# MUSB_05_X_B_SM_A.net
KiCad netlist of a schematic drawn in Altium Designer
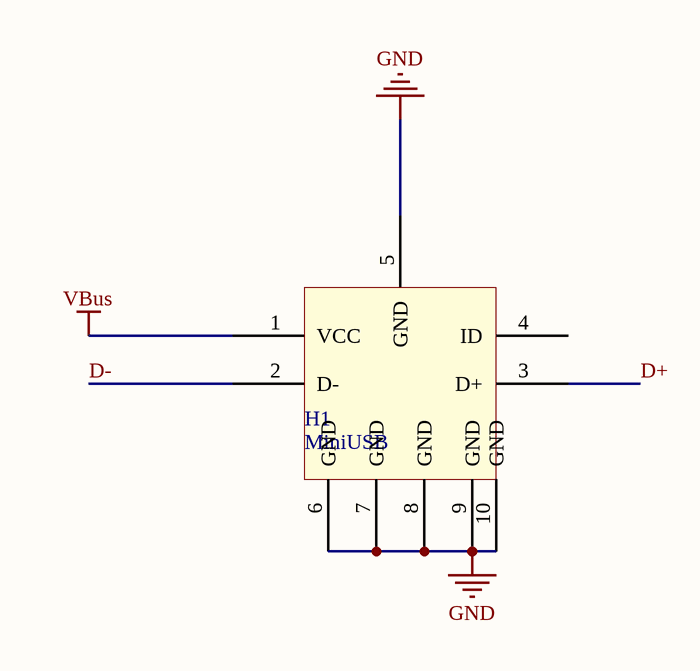
[diagram p0: MUSB_05_X_B_SM_A.SchDoc]

(export (version "E")
  (design (tool "Eeschema 10.0.6"))
  (components
    (comp (ref "H1")
      (value "MiniUSB")
      (footprint "MiniUSB")
      (libsource (lib "MUSB_05_X_B_SM_A") (part "MiniUSB"))
    )
  )
  (nets
    (net (code "1") (name "/D+") (class "Default")
      (node (ref "H1") (pin "3") (pinfunction "D+_3") (pintype "passive"))
    )
    (net (code "2") (name "/D-") (class "Default")
      (node (ref "H1") (pin "2") (pinfunction "D-_2") (pintype "passive"))
    )
    (net (code "3") (name "GND") (class "Default")
      (node (ref "H1") (pin "10") (pinfunction "GND_10") (pintype "passive"))
      (node (ref "H1") (pin "5") (pinfunction "GND_5") (pintype "passive"))
      (node (ref "H1") (pin "6") (pinfunction "GND_6") (pintype "passive"))
      (node (ref "H1") (pin "7") (pinfunction "GND_7") (pintype "passive"))
      (node (ref "H1") (pin "8") (pinfunction "GND_8") (pintype "passive"))
      (node (ref "H1") (pin "9") (pinfunction "GND_9") (pintype "passive"))
    )
    (net (code "4") (name "VBus") (class "Default")
      (node (ref "H1") (pin "1") (pinfunction "VCC_1") (pintype "passive"))
    )
    (net (code "5") (name "unconnected-(H1-ID-Pad4)") (class "Default")
      (node (ref "H1") (pin "4") (pinfunction "ID_4") (pintype "passive"))
    )
  )
)
